# RFD900module.net
KiCad netlist of a schematic drawn in EAGLE
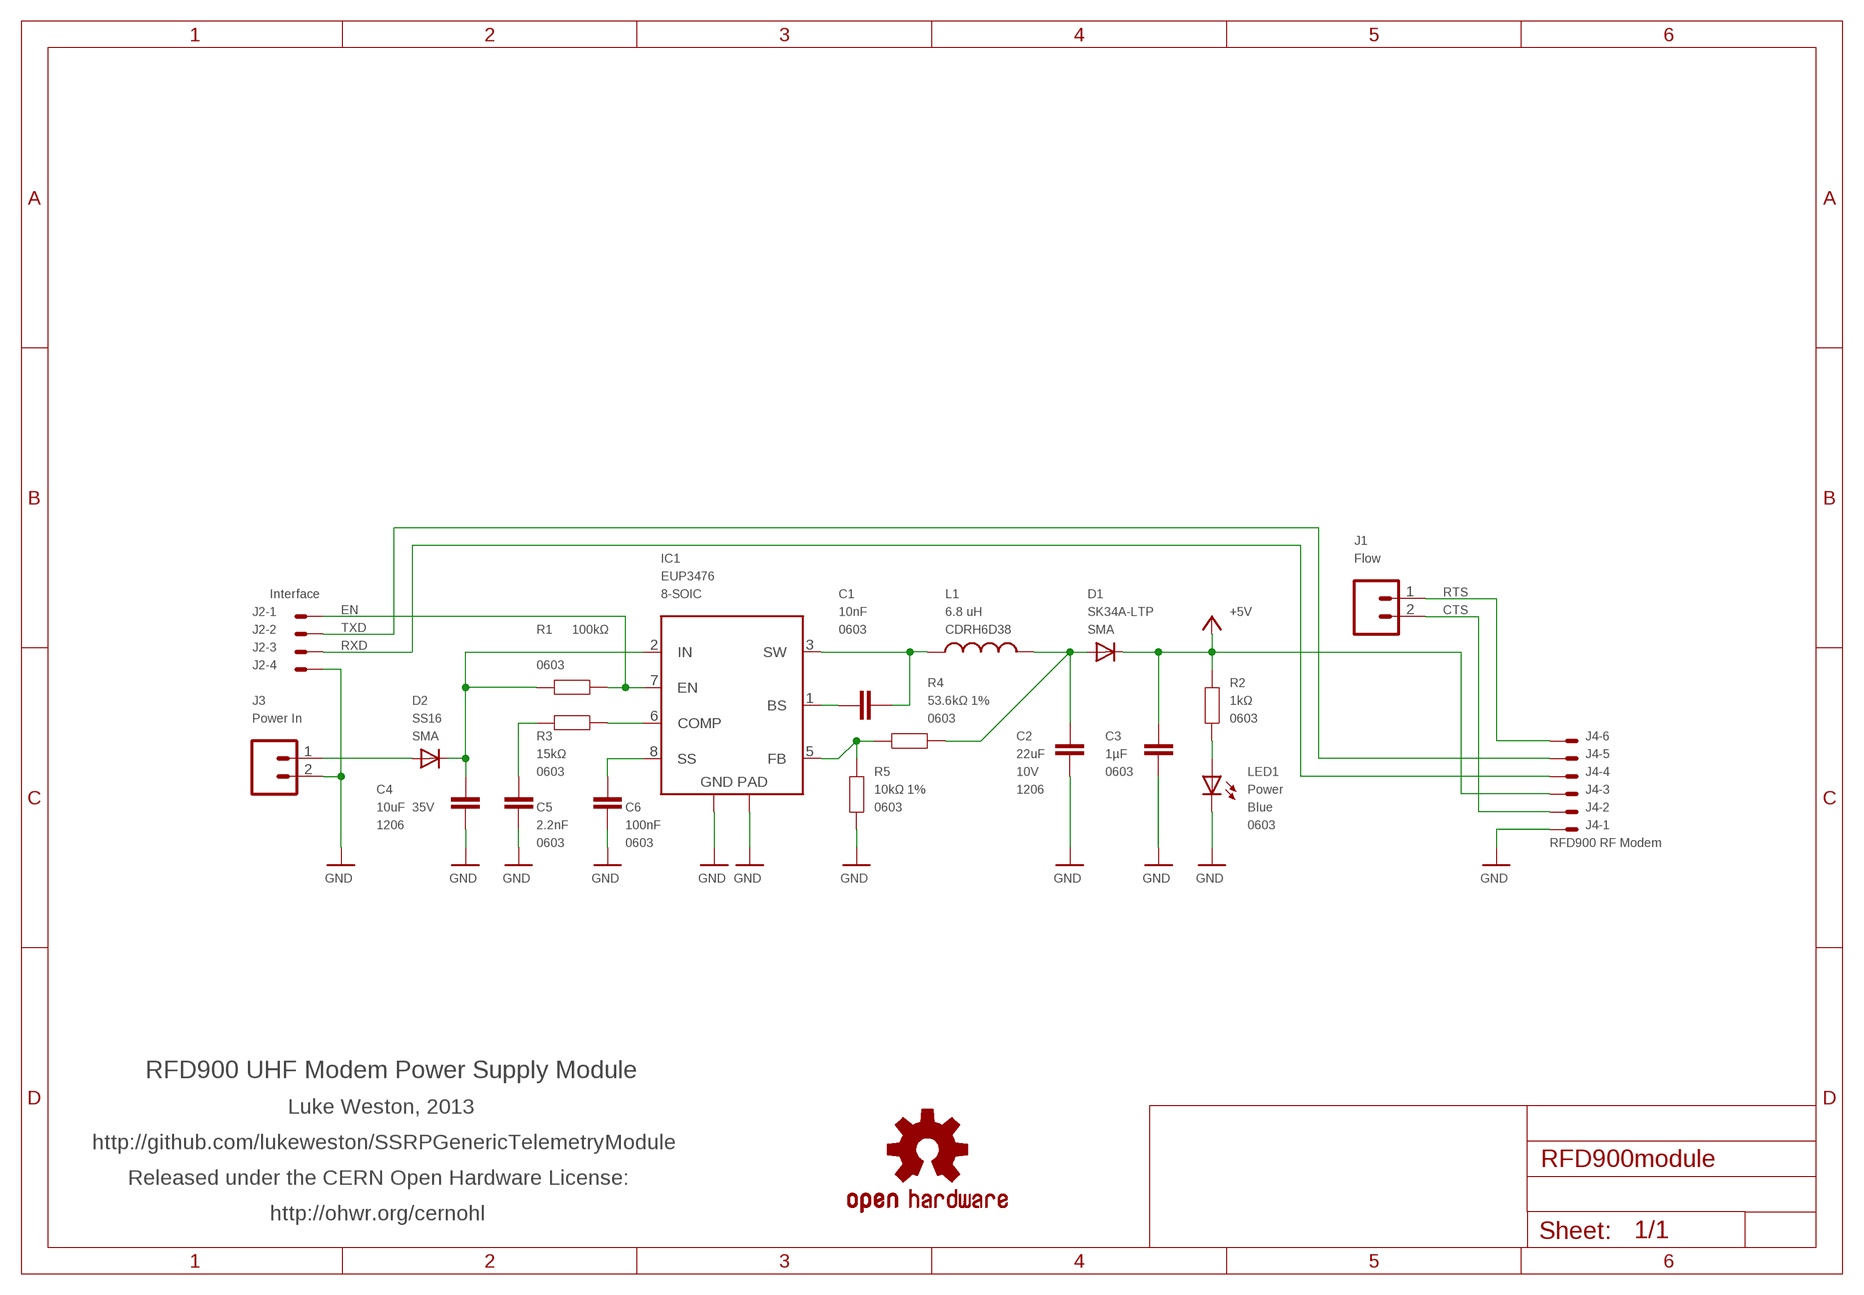
[diagram p0: schematic, sheet 1]

(export (version "E")
  (design (tool "Eeschema 10.0.6"))
  (components
    (comp (ref "C1")
      (value "10nF")
      (footprint "eagle-import:0603")
      (fields (field (name "PACKAGE") "0603"))
      (libsource (lib "eagle-import") (part "CAP0603"))
    )
    (comp (ref "C2")
      (value "22uF")
      (footprint "eagle-import:C1206")
      (fields (field (name "PACKAGE") "1206") (field (name "VOLTAGE") "10V"))
      (libsource (lib "eagle-import") (part "C-EUC1206"))
    )
    (comp (ref "C3")
      (value "1µF")
      (footprint "eagle-import:0603")
      (fields (field (name "PACKAGE") "0603"))
      (libsource (lib "eagle-import") (part "CAP0603"))
    )
    (comp (ref "C4")
      (value "10uF")
      (footprint "eagle-import:C1206")
      (fields (field (name "PACKAGE") "1206") (field (name "VOLTAGE") "35V"))
      (libsource (lib "eagle-import") (part "C-EUC1206"))
    )
    (comp (ref "C5")
      (value "2.2nF")
      (footprint "eagle-import:0603")
      (fields (field (name "PACKAGE") "0603"))
      (libsource (lib "eagle-import") (part "CAP0603"))
    )
    (comp (ref "C6")
      (value "100nF")
      (footprint "eagle-import:0603")
      (fields (field (name "PACKAGE") "0603"))
      (libsource (lib "eagle-import") (part "CAP0603"))
    )
    (comp (ref "D1")
      (value "SK34A-LTP")
      (footprint "eagle-import:SMA-DIODE")
      (fields (field (name "PACKAGE") "SMA"))
      (libsource (lib "eagle-import") (part "freetronics-master-v1_DIODESMA"))
    )
    (comp (ref "D2")
      (value "SS16")
      (footprint "eagle-import:SMA-SMB-DIODE")
      (fields (field (name "PACKAGE") "SMA"))
      (libsource (lib "eagle-import") (part "DIODESMAB"))
    )
    (comp (ref "IC1")
      (value "EUP3476")
      (footprint "eagle-import:SO08T")
      (fields (field (name "PACKAGE") "8-SOIC"))
      (libsource (lib "eagle-import") (part "EUP3476"))
    )
    (comp (ref "J1")
      (value "Flow")
      (footprint "eagle-import:1X02")
      (libsource (lib "eagle-import") (part "M02PTH"))
    )
    (comp (ref "J2")
      (value "Interface")
      (footprint "eagle-import:7395-04")
      (libsource (lib "eagle-import") (part "22-?-0405-7048"))
    )
    (comp (ref "J3")
      (value "Power In")
      (footprint "eagle-import:SCREWTERMINAL-3.5MM-2")
      (libsource (lib "eagle-import") (part "M023.5MM"))
    )
    (comp (ref "J4")
      (value "RFD900 RF Modem")
      (footprint "eagle-import:7395-06")
      (libsource (lib "eagle-import") (part "22-?-0605-7068"))
    )
    (comp (ref "L1")
      (value "6.8 uH")
      (footprint "eagle-import:CDRH")
      (fields (field (name "SKU") "CDRH6D38"))
      (libsource (lib "eagle-import") (part "INDUCTOR"))
    )
    (comp (ref "LED1")
      (value "Power")
      (footprint "eagle-import:LED-0603")
      (fields (field (name "COLOUR") "Blue") (field (name "PACKAGE") "0603"))
      (libsource (lib "eagle-import") (part "LED0603"))
    )
    (comp (ref "R1")
      (value "100kΩ")
      (footprint "eagle-import:0603")
      (fields (field (name "PACKAGE") "0603"))
      (libsource (lib "eagle-import") (part "RESISTOR0603"))
    )
    (comp (ref "R2")
      (value "1kΩ")
      (footprint "eagle-import:0603")
      (fields (field (name "PACKAGE") "0603"))
      (libsource (lib "eagle-import") (part "RESISTOR0603"))
    )
    (comp (ref "R3")
      (value "15kΩ")
      (footprint "eagle-import:0603")
      (fields (field (name "PACKAGE") "0603"))
      (libsource (lib "eagle-import") (part "RESISTOR0603"))
    )
    (comp (ref "R4")
      (value "53.6kΩ 1%")
      (footprint "eagle-import:0603")
      (fields (field (name "PACKAGE") "0603"))
      (libsource (lib "eagle-import") (part "RESISTOR0603"))
    )
    (comp (ref "R5")
      (value "10kΩ 1%")
      (footprint "eagle-import:0603")
      (fields (field (name "PACKAGE") "0603"))
      (libsource (lib "eagle-import") (part "RESISTOR0603"))
    )
    (comp (ref "SY")
      (value "OSHW-LOGOS")
      (footprint "eagle-import:OSHW-LOGO-S")
      (libsource (lib "eagle-import") (part "OSHW-LOGOS"))
    )
  )
  (nets
    (net (code "1") (name "+5V") (class "Default")
      (node (ref "C3") (pin "2") (pinfunction "2_2") (pintype "passive"))
      (node (ref "D1") (pin "C") (pinfunction "C_C") (pintype "passive"))
      (node (ref "J4") (pin "3") (pinfunction "S_3") (pintype "passive"))
      (node (ref "R2") (pin "1") (pinfunction "1_1") (pintype "passive"))
    )
    (net (code "2") (name "/CTS") (class "Default")
      (node (ref "J1") (pin "2") (pinfunction "2_2") (pintype "passive"))
      (node (ref "J4") (pin "2") (pinfunction "S_2") (pintype "passive"))
    )
    (net (code "3") (name "/EN") (class "Default")
      (node (ref "IC1") (pin "7") (pinfunction "EN_7") (pintype "input"))
      (node (ref "J2") (pin "1") (pinfunction "S_1") (pintype "passive"))
      (node (ref "R1") (pin "1") (pinfunction "1_1") (pintype "passive"))
    )
    (net (code "4") (name "/RTS") (class "Default")
      (node (ref "J1") (pin "1") (pinfunction "1_1") (pintype "passive"))
      (node (ref "J4") (pin "6") (pinfunction "S_6") (pintype "passive"))
    )
    (net (code "5") (name "/RXD") (class "Default")
      (node (ref "J2") (pin "3") (pinfunction "S_3") (pintype "passive"))
      (node (ref "J4") (pin "4") (pinfunction "S_4") (pintype "passive"))
    )
    (net (code "6") (name "/TXD") (class "Default")
      (node (ref "J2") (pin "2") (pinfunction "S_2") (pintype "passive"))
      (node (ref "J4") (pin "5") (pinfunction "S_5") (pintype "passive"))
    )
    (net (code "7") (name "GND") (class "Default")
      (node (ref "C2") (pin "2") (pinfunction "2_2") (pintype "passive"))
      (node (ref "C3") (pin "1") (pinfunction "1_1") (pintype "passive"))
      (node (ref "C4") (pin "2") (pinfunction "2_2") (pintype "passive"))
      (node (ref "C5") (pin "1") (pinfunction "1_1") (pintype "passive"))
      (node (ref "C6") (pin "1") (pinfunction "1_1") (pintype "passive"))
      (node (ref "IC1") (pin "4") (pinfunction "GND_4") (pintype "power_in"))
      (node (ref "IC1") (pin "9") (pinfunction "TGND_9") (pintype "power_in"))
      (node (ref "J2") (pin "4") (pinfunction "S_4") (pintype "passive"))
      (node (ref "J3") (pin "2") (pinfunction "2_2") (pintype "passive"))
      (node (ref "J4") (pin "1") (pinfunction "S_1") (pintype "passive"))
      (node (ref "LED1") (pin "C") (pinfunction "C_C") (pintype "passive"))
      (node (ref "R5") (pin "2") (pinfunction "2_2") (pintype "passive"))
    )
    (net (code "8") (name "Net-(C2-Pad1)") (class "Default")
      (node (ref "C2") (pin "1") (pinfunction "1_1") (pintype "passive"))
      (node (ref "D1") (pin "A") (pinfunction "A_A") (pintype "passive"))
      (node (ref "L1") (pin "2") (pinfunction "2_2") (pintype "bidirectional"))
      (node (ref "R4") (pin "2") (pinfunction "2_2") (pintype "passive"))
    )
    (net (code "9") (name "Net-(C5-Pad2)") (class "Default")
      (node (ref "C5") (pin "2") (pinfunction "2_2") (pintype "passive"))
      (node (ref "R3") (pin "2") (pinfunction "2_2") (pintype "passive"))
    )
    (net (code "10") (name "Net-(D2-PadA)") (class "Default")
      (node (ref "D2") (pin "A") (pinfunction "A_A") (pintype "passive"))
      (node (ref "J3") (pin "1") (pinfunction "1_1") (pintype "passive"))
    )
    (net (code "11") (name "Net-(IC1-BS)") (class "Default")
      (node (ref "C1") (pin "2") (pinfunction "2_2") (pintype "passive"))
      (node (ref "IC1") (pin "1") (pinfunction "BS_1") (pintype "bidirectional"))
    )
    (net (code "12") (name "Net-(IC1-COMP)") (class "Default")
      (node (ref "IC1") (pin "6") (pinfunction "COMP_6") (pintype "bidirectional"))
      (node (ref "R3") (pin "1") (pinfunction "1_1") (pintype "passive"))
    )
    (net (code "13") (name "Net-(IC1-FB)") (class "Default")
      (node (ref "IC1") (pin "5") (pinfunction "FB_5") (pintype "bidirectional"))
      (node (ref "R4") (pin "1") (pinfunction "1_1") (pintype "passive"))
      (node (ref "R5") (pin "1") (pinfunction "1_1") (pintype "passive"))
    )
    (net (code "14") (name "Net-(IC1-IN)") (class "Default")
      (node (ref "C4") (pin "1") (pinfunction "1_1") (pintype "passive"))
      (node (ref "D2") (pin "C") (pinfunction "C_C") (pintype "passive"))
      (node (ref "IC1") (pin "2") (pinfunction "IN_2") (pintype "power_in"))
      (node (ref "R1") (pin "2") (pinfunction "2_2") (pintype "passive"))
    )
    (net (code "15") (name "Net-(IC1-SS)") (class "Default")
      (node (ref "C6") (pin "2") (pinfunction "2_2") (pintype "passive"))
      (node (ref "IC1") (pin "8") (pinfunction "SS_8") (pintype "bidirectional"))
    )
    (net (code "16") (name "Net-(IC1-SW)") (class "Default")
      (node (ref "C1") (pin "1") (pinfunction "1_1") (pintype "passive"))
      (node (ref "IC1") (pin "3") (pinfunction "SW_3") (pintype "bidirectional"))
      (node (ref "L1") (pin "1") (pinfunction "1_1") (pintype "bidirectional"))
    )
    (net (code "17") (name "Net-(LED1-PadA)") (class "Default")
      (node (ref "LED1") (pin "A") (pinfunction "A_A") (pintype "passive"))
      (node (ref "R2") (pin "2") (pinfunction "2_2") (pintype "passive"))
    )
  )
)
